# Spectre-Analyzer-SCH_SH2__C.net
KiCad netlist of a schematic drawn in Altium Designer
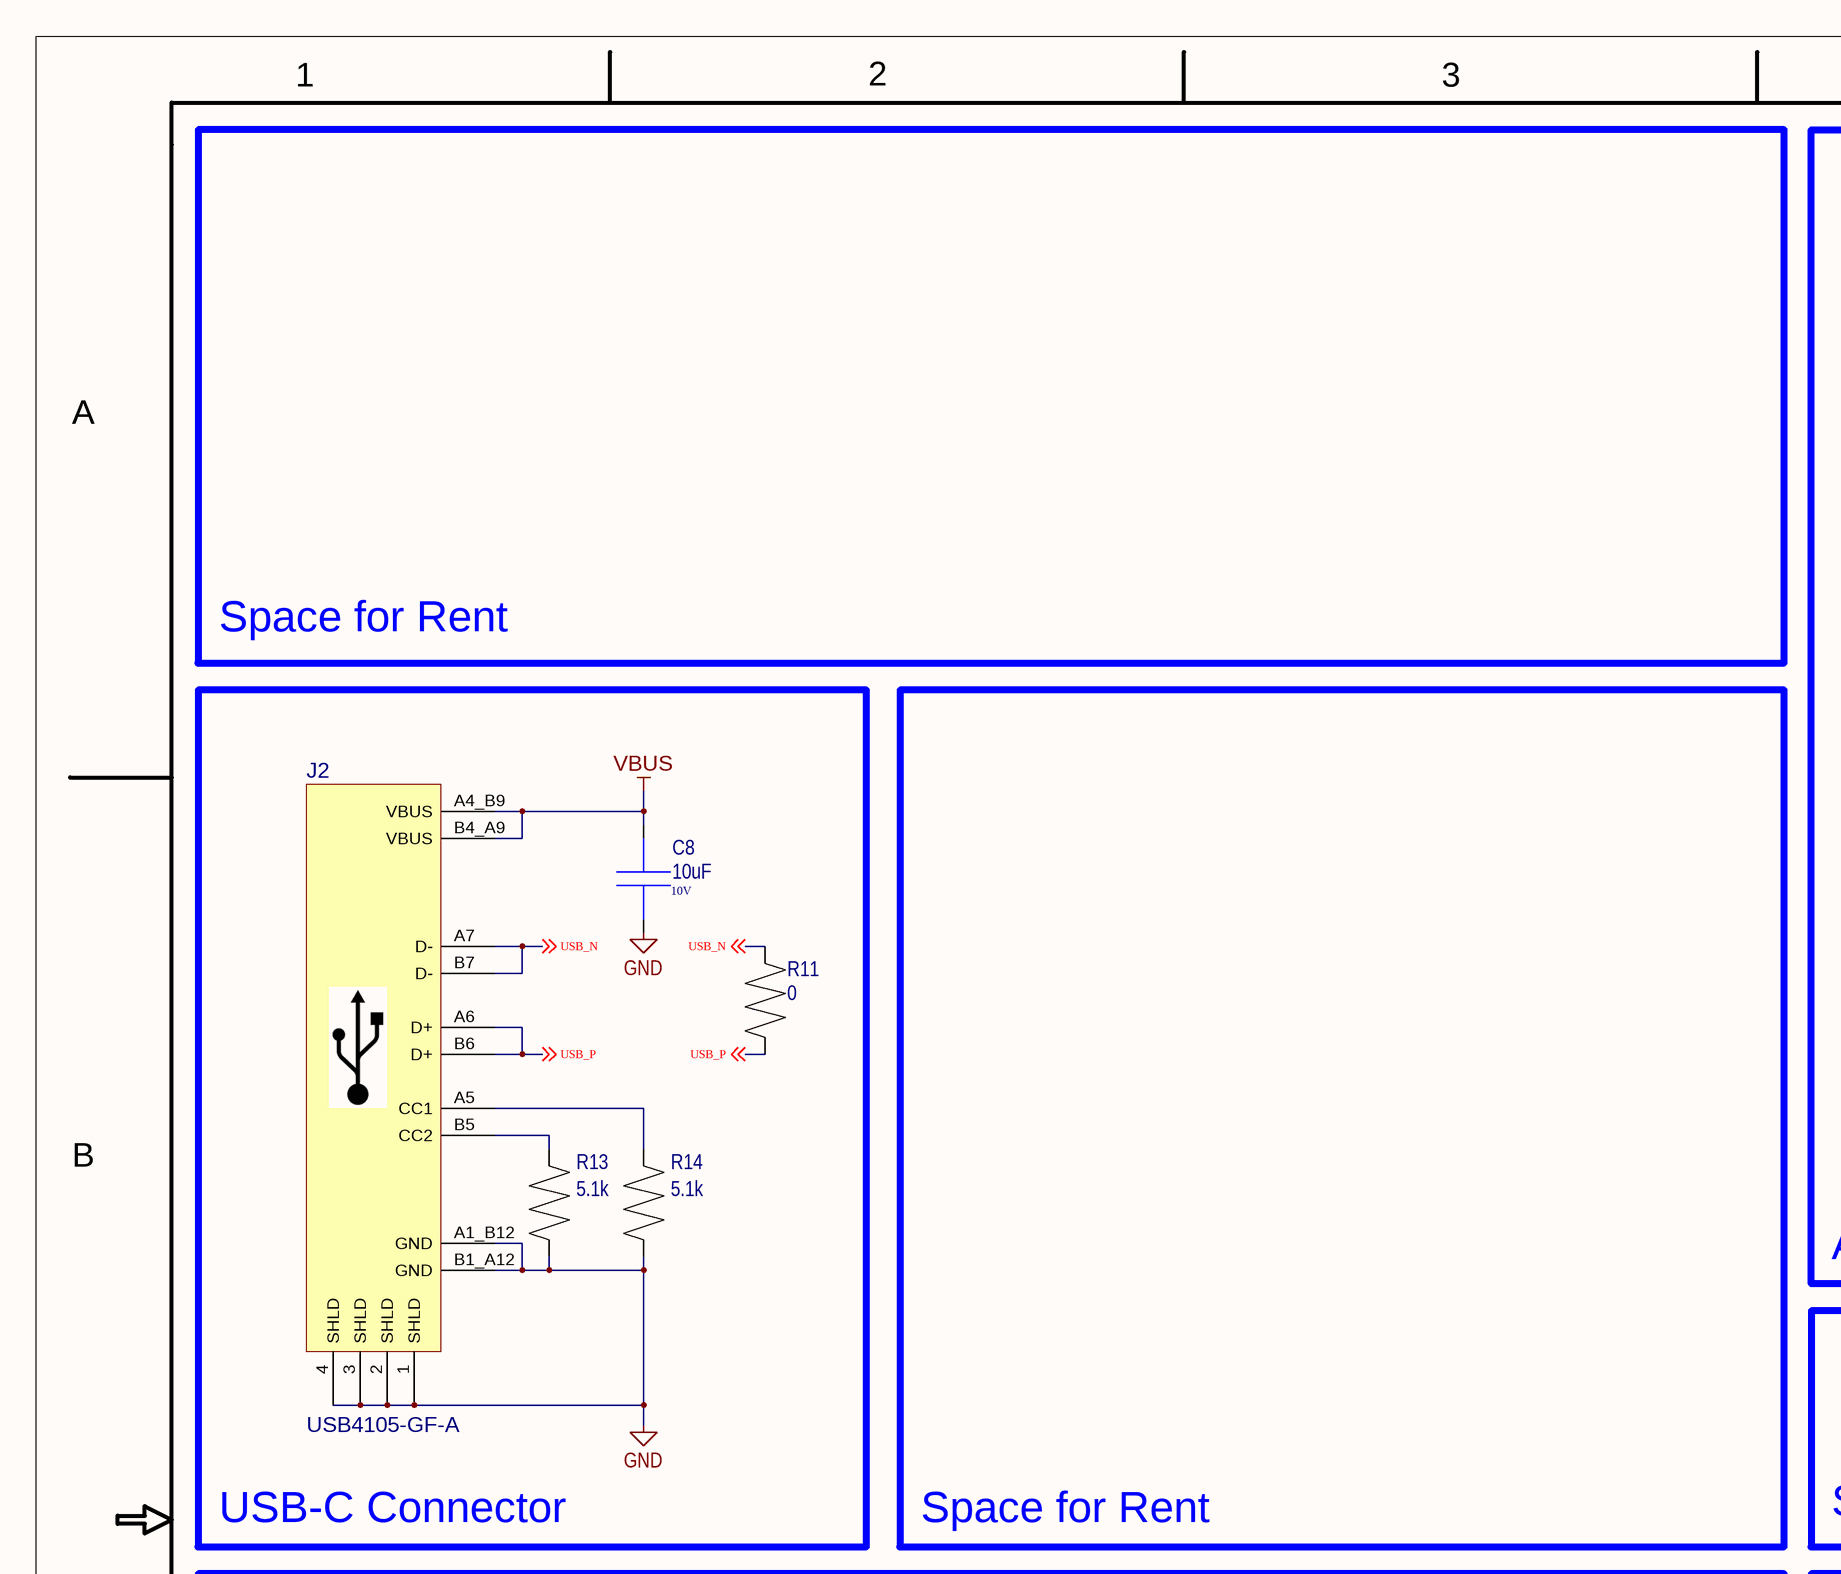
[diagram p0: Spectre-Analyzer-SCH_SH2_(C).SchDoc, top left]
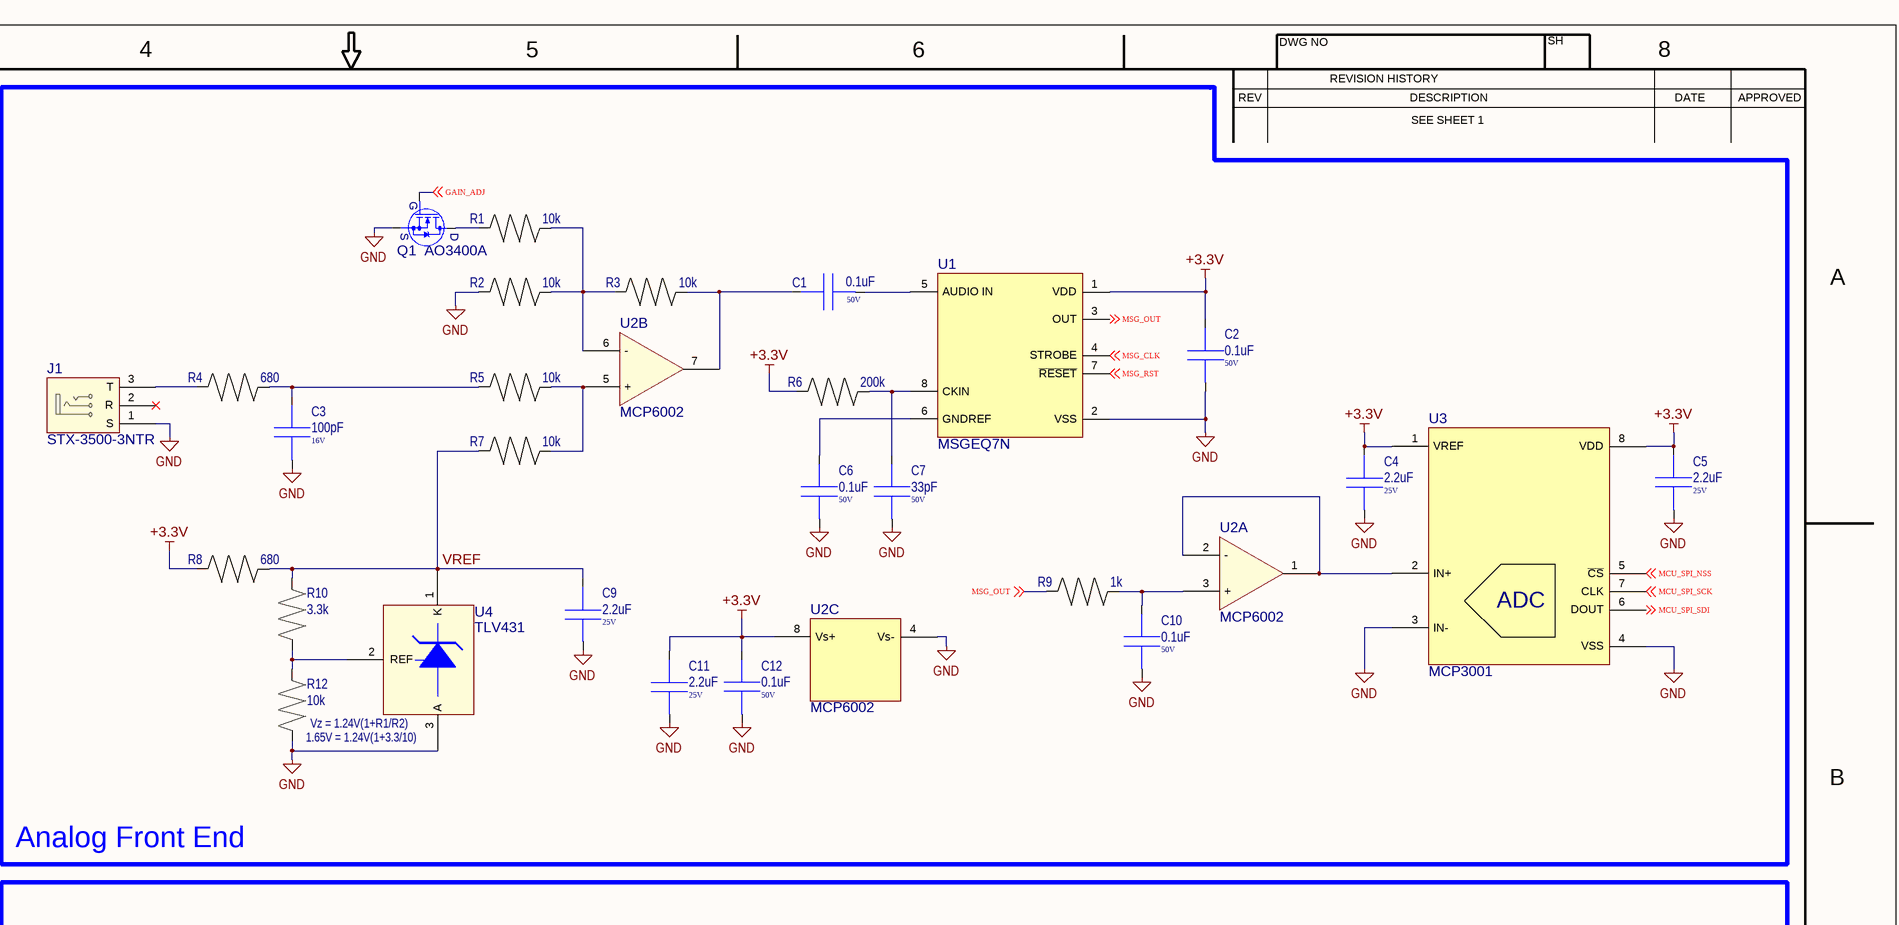
[diagram p1: Spectre-Analyzer-SCH_SH2_(C).SchDoc, top right]
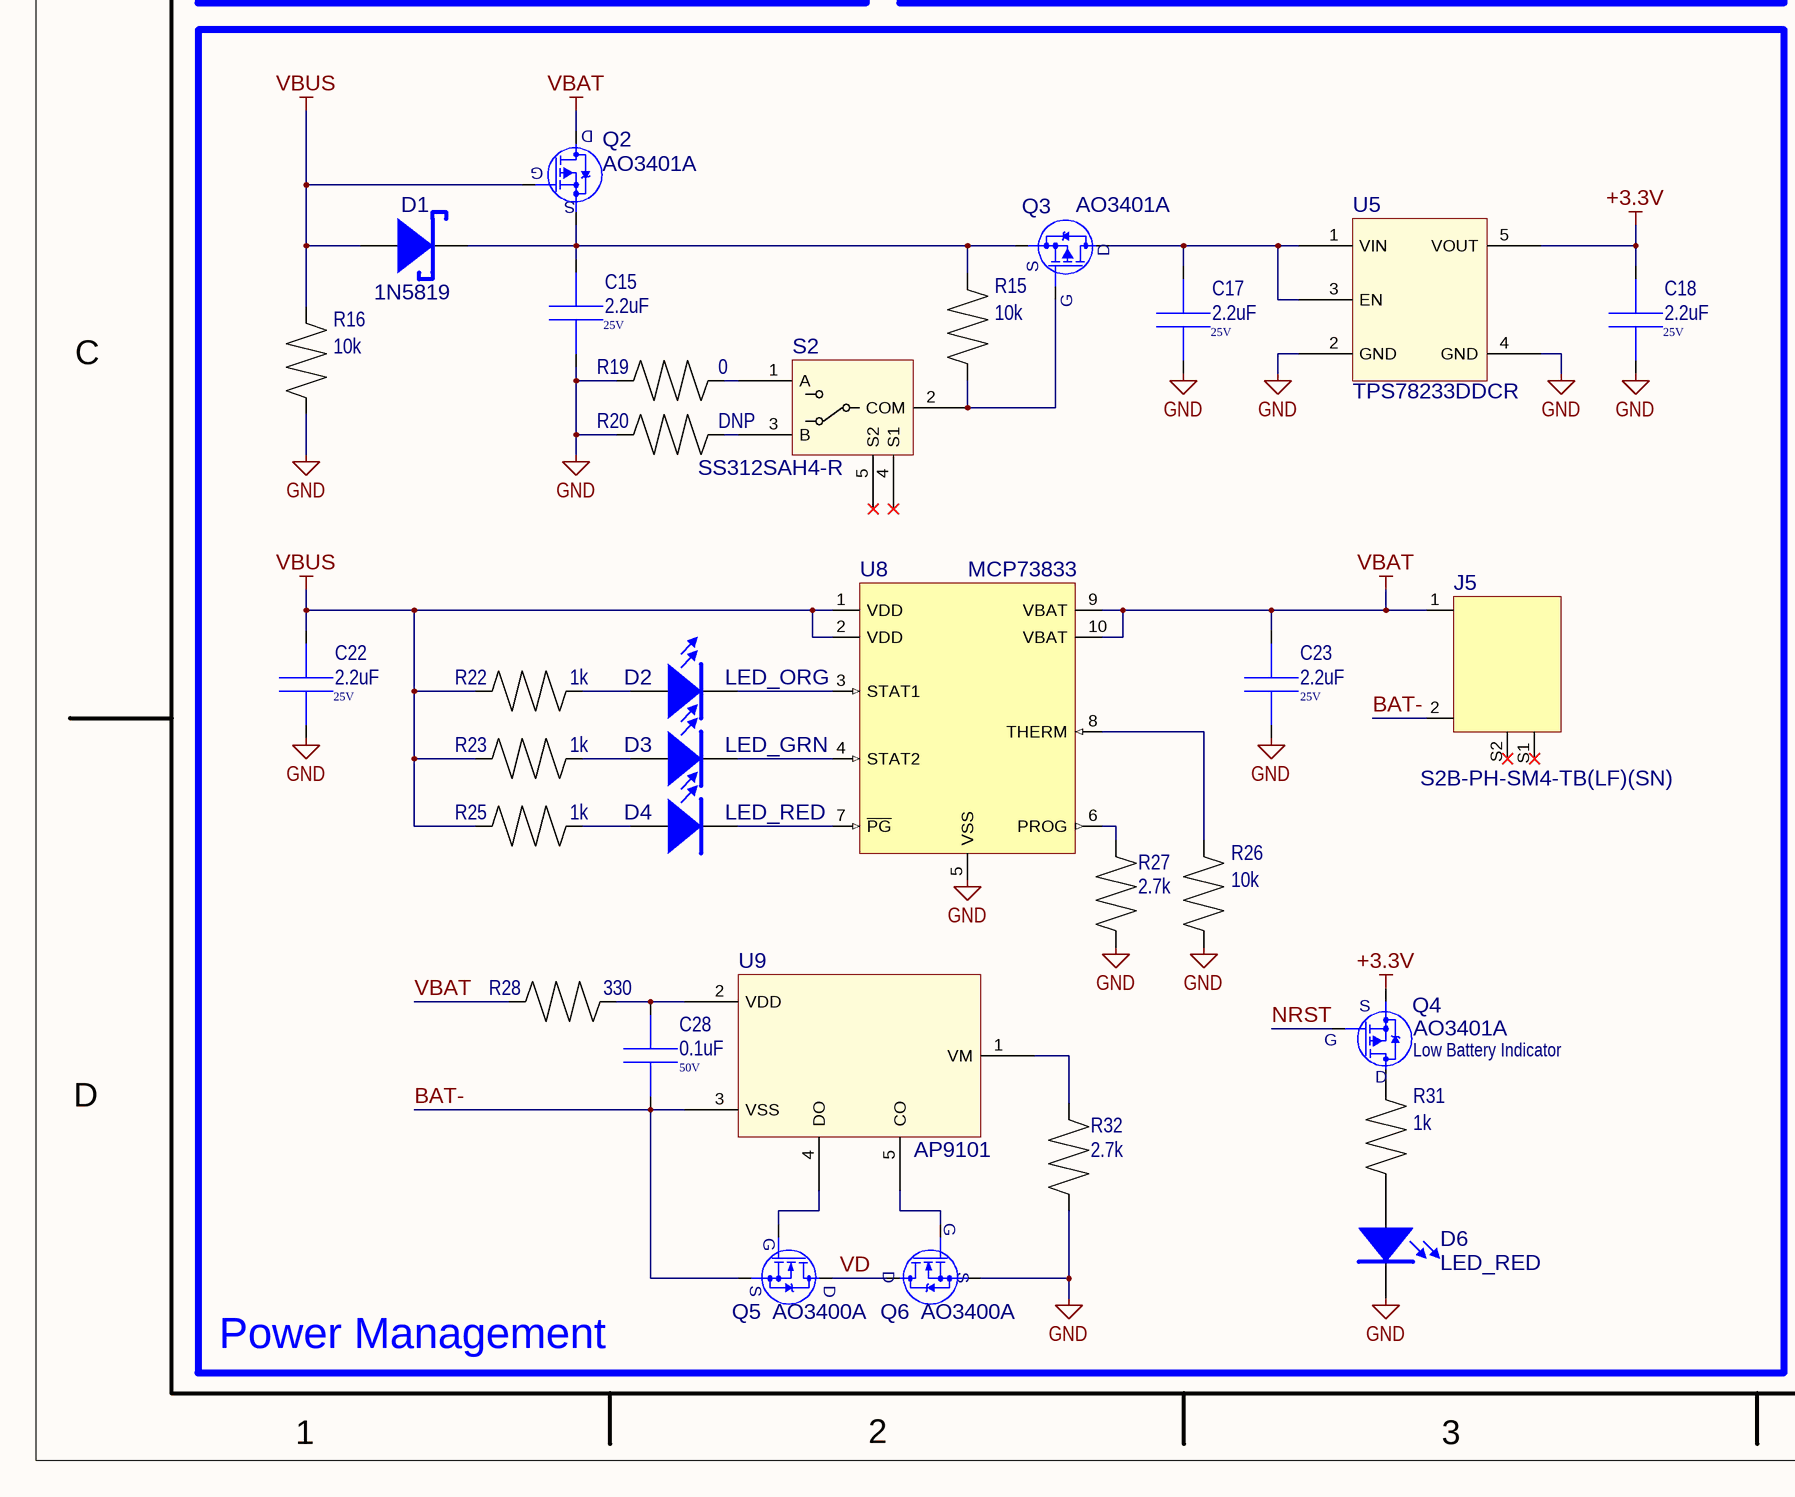
[diagram p2: Spectre-Analyzer-SCH_SH2_(C).SchDoc, bottom left]
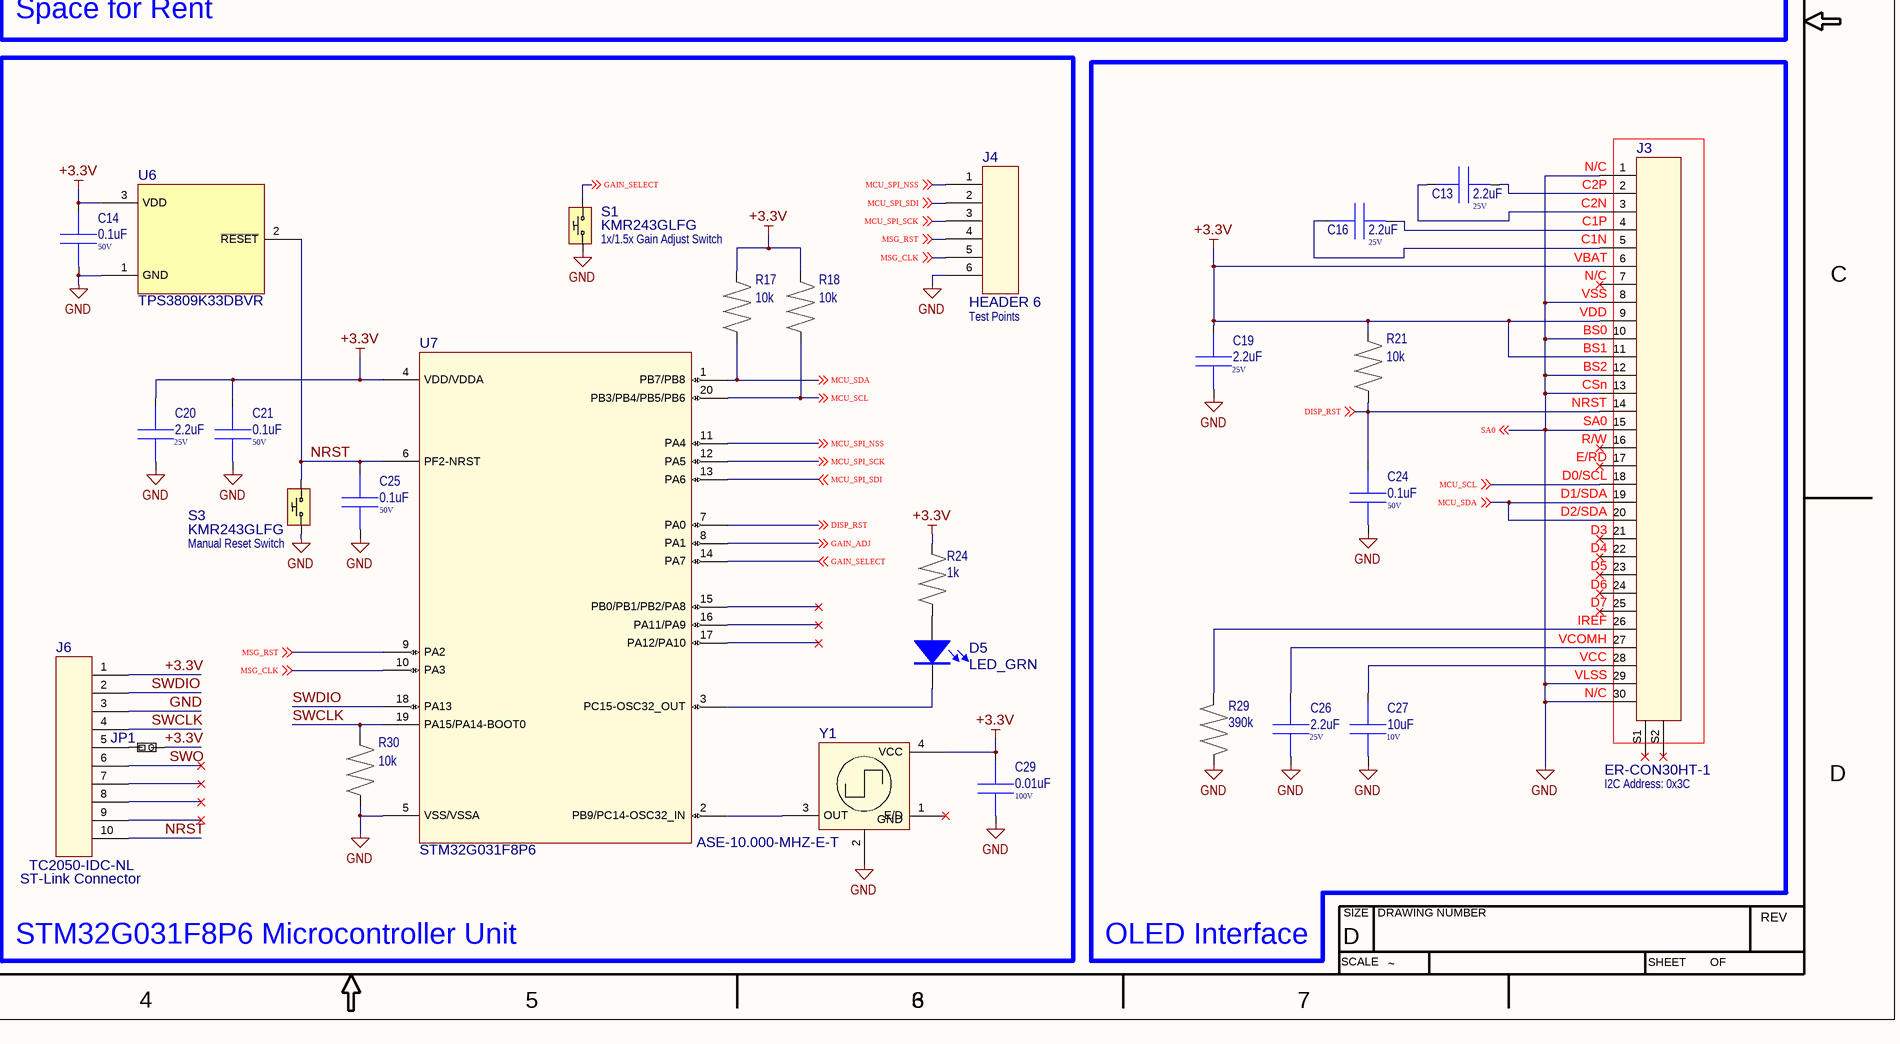
[diagram p3: Spectre-Analyzer-SCH_SH2_(C).SchDoc, bottom right]

(export (version "E")
  (design (tool "Eeschema 10.0.6"))
  (components
    (comp (ref "C1")
      (value "0.1uF")
      (footprint "0402")
      (description "CAP CER 0.1UF 50V X7R 0402")
      (fields
        (field (name "PART NUMBER") "UMK105B7104KVHF")
        (field (name "MANUFACTURER") "Taiyo Yuden")
        (field (name "VOLTAGE") "50V")
      )
      (libsource (lib "CAPACITORS") (part "CAP"))
    )
    (comp (ref "C2")
      (value "0.1uF")
      (footprint "0402")
      (description "CAP CER 0.1UF 50V X7R 0402")
      (fields
        (field (name "PART NUMBER") "UMK105B7104KVHF")
        (field (name "MANUFACTURER") "Taiyo Yuden")
        (field (name "VOLTAGE") "50V")
      )
      (libsource (lib "CAPACITORS") (part "CAP"))
    )
    (comp (ref "C3")
      (value "100pF")
      (footprint "0402")
      (description "CAP CER 100PF 16V X7R 0402")
      (fields
        (field (name "PART NUMBER") "VJ0402Y101KXJCW1BC")
        (field (name "MANUFACTURER") "Vishay Vitramon")
        (field (name "VOLTAGE") "16V")
      )
      (libsource (lib "CAPACITORS") (part "CAP"))
    )
    (comp (ref "C4")
      (value "2.2uF")
      (footprint "0402")
      (description "CAP CER 2.2UF 25V X5R 0402")
      (fields
        (field (name "PART NUMBER") "GRM155R61E225KE11D")
        (field (name "MANUFACTURER") "Murata Electronics")
        (field (name "VOLTAGE") "25V")
      )
      (libsource (lib "CAPACITORS") (part "CAP"))
    )
    (comp (ref "C5")
      (value "2.2uF")
      (footprint "0402")
      (description "CAP CER 2.2UF 25V X5R 0402")
      (fields
        (field (name "PART NUMBER") "GRM155R61E225KE11D")
        (field (name "MANUFACTURER") "Murata Electronics")
        (field (name "VOLTAGE") "25V")
      )
      (libsource (lib "CAPACITORS") (part "CAP"))
    )
    (comp (ref "C6")
      (value "0.1uF")
      (footprint "0402")
      (description "CAP CER 0.1UF 50V X7R 0402")
      (fields
        (field (name "PART NUMBER") "UMK105B7104KVHF")
        (field (name "MANUFACTURER") "Taiyo Yuden")
        (field (name "VOLTAGE") "50V")
      )
      (libsource (lib "CAPACITORS") (part "CAP"))
    )
    (comp (ref "C7")
      (value "33pF")
      (footprint "0402")
      (description "CAP CER 33PF 50V X7R 0402")
      (fields
        (field (name "PART NUMBER") "04025C330JAT2A")
        (field (name "MANUFACTURER") "KYOCERA AVX")
        (field (name "VOLTAGE") "50V")
      )
      (libsource (lib "CAPACITORS") (part "CAP"))
    )
    (comp (ref "C8")
      (value "10uF")
      (footprint "0402")
      (description "CAP CER 10UF 10V X5R 0402")
      (fields
        (field (name "PART NUMBER") "CL05A106MP5NUNC")
        (field (name "MANUFACTURER") "Samsung Electro-Mechanics")
        (field (name "VOLTAGE") "10V")
      )
      (libsource (lib "CAPACITORS") (part "CAP"))
    )
    (comp (ref "C9")
      (value "2.2uF")
      (footprint "0402")
      (description "CAP CER 2.2UF 25V X5R 0402")
      (fields
        (field (name "PART NUMBER") "GRM155R61E225KE11D")
        (field (name "MANUFACTURER") "Murata Electronics")
        (field (name "VOLTAGE") "25V")
      )
      (libsource (lib "CAPACITORS") (part "CAP"))
    )
    (comp (ref "C10")
      (value "0.1uF")
      (footprint "0402")
      (description "CAP CER 0.1UF 50V X7R 0402")
      (fields
        (field (name "PART NUMBER") "UMK105B7104KVHF")
        (field (name "MANUFACTURER") "Taiyo Yuden")
        (field (name "VOLTAGE") "50V")
      )
      (libsource (lib "CAPACITORS") (part "CAP"))
    )
    (comp (ref "C11")
      (value "2.2uF")
      (footprint "0402")
      (description "CAP CER 2.2UF 25V X5R 0402")
      (fields
        (field (name "PART NUMBER") "GRM155R61E225KE11D")
        (field (name "MANUFACTURER") "Murata Electronics")
        (field (name "VOLTAGE") "25V")
      )
      (libsource (lib "CAPACITORS") (part "CAP"))
    )
    (comp (ref "C12")
      (value "0.1uF")
      (footprint "0402")
      (description "CAP CER 0.1UF 50V X7R 0402")
      (fields
        (field (name "PART NUMBER") "UMK105B7104KVHF")
        (field (name "MANUFACTURER") "Taiyo Yuden")
        (field (name "VOLTAGE") "50V")
      )
      (libsource (lib "CAPACITORS") (part "CAP"))
    )
    (comp (ref "C13")
      (value "2.2uF")
      (footprint "0402")
      (description "CAP CER 2.2UF 25V X5R 0402")
      (fields
        (field (name "PART NUMBER") "GRM188C81A106MA73D")
        (field (name "MANUFACTURER") "Murata Electronics")
        (field (name "VOLTAGE") "25V")
      )
      (libsource (lib "CAPACITORS") (part "CAP"))
    )
    (comp (ref "C14")
      (value "0.1uF")
      (footprint "0402")
      (description "CAP CER 0.1UF 50V X7R 0402")
      (fields
        (field (name "PART NUMBER") "UMK105B7104KVHF")
        (field (name "MANUFACTURER") "Taiyo Yuden")
        (field (name "VOLTAGE") "50V")
      )
      (libsource (lib "CAPACITORS") (part "CAP"))
    )
    (comp (ref "C15")
      (value "2.2uF")
      (footprint "0402")
      (description "CAP CER 2.2UF 25V X5R 0402")
      (fields
        (field (name "PART NUMBER") "GRM155R61E225KE11D")
        (field (name "MANUFACTURER") "Murata Electronics")
        (field (name "VOLTAGE") "25V")
      )
      (libsource (lib "CAPACITORS") (part "CAP"))
    )
    (comp (ref "C16")
      (value "2.2uF")
      (footprint "0402")
      (description "CAP CER 2.2UF 25V X5R 0402")
      (fields
        (field (name "PART NUMBER") "GRM188C81A106MA73D")
        (field (name "MANUFACTURER") "Murata Electronics")
        (field (name "VOLTAGE") "25V")
      )
      (libsource (lib "CAPACITORS") (part "CAP"))
    )
    (comp (ref "C17")
      (value "2.2uF")
      (footprint "0402")
      (description "CAP CER 2.2UF 25V X5R 0402")
      (fields
        (field (name "PART NUMBER") "GRM155R61E225KE11D")
        (field (name "MANUFACTURER") "Murata Electronics")
        (field (name "VOLTAGE") "25V")
      )
      (libsource (lib "CAPACITORS") (part "CAP"))
    )
    (comp (ref "C18")
      (value "2.2uF")
      (footprint "0402")
      (description "CAP CER 2.2UF 25V X5R 0402")
      (fields
        (field (name "PART NUMBER") "GRM155R61E225KE11D")
        (field (name "MANUFACTURER") "Murata Electronics")
        (field (name "VOLTAGE") "25V")
      )
      (libsource (lib "CAPACITORS") (part "CAP"))
    )
    (comp (ref "C19")
      (value "2.2uF")
      (footprint "0402")
      (description "CAP CER 2.2UF 25V X5R 0402")
      (fields
        (field (name "PART NUMBER") "GRM188C81A106MA73D")
        (field (name "MANUFACTURER") "Murata Electronics")
        (field (name "VOLTAGE") "25V")
      )
      (libsource (lib "CAPACITORS") (part "CAP"))
    )
    (comp (ref "C20")
      (value "2.2uF")
      (footprint "0402")
      (description "CAP CER 2.2UF 25V X5R 0402")
      (fields
        (field (name "PART NUMBER") "GRM155R61E225KE11D")
        (field (name "MANUFACTURER") "Murata Electronics")
        (field (name "VOLTAGE") "25V")
      )
      (libsource (lib "CAPACITORS") (part "CAP"))
    )
    (comp (ref "C21")
      (value "0.1uF")
      (footprint "0402")
      (description "CAP CER 0.1UF 50V X7R 0402")
      (fields
        (field (name "PART NUMBER") "UMK105B7104KVHF")
        (field (name "MANUFACTURER") "Taiyo Yuden")
        (field (name "VOLTAGE") "50V")
      )
      (libsource (lib "CAPACITORS") (part "CAP"))
    )
    (comp (ref "C22")
      (value "2.2uF")
      (footprint "0402")
      (description "CAP CER 2.2UF 25V X5R 0402")
      (fields
        (field (name "PART NUMBER") "GRM155R61E225KE11D")
        (field (name "MANUFACTURER") "Murata Electronics")
        (field (name "VOLTAGE") "25V")
      )
      (libsource (lib "CAPACITORS") (part "CAP"))
    )
    (comp (ref "C23")
      (value "2.2uF")
      (footprint "0402")
      (description "CAP CER 2.2UF 25V X5R 0402")
      (fields
        (field (name "PART NUMBER") "GRM155R61E225KE11D")
        (field (name "MANUFACTURER") "Murata Electronics")
        (field (name "VOLTAGE") "25V")
      )
      (libsource (lib "CAPACITORS") (part "CAP"))
    )
    (comp (ref "C24")
      (value "0.1uF")
      (footprint "0402")
      (description "CAP CER 0.1UF 50V X7R 0402")
      (fields
        (field (name "PART NUMBER") "UMK105B7104KVHF")
        (field (name "MANUFACTURER") "Taiyo Yuden")
        (field (name "VOLTAGE") "50V")
      )
      (libsource (lib "CAPACITORS") (part "CAP"))
    )
    (comp (ref "C25")
      (value "0.1uF")
      (footprint "0402")
      (description "CAP CER 0.1UF 50V X7R 0402")
      (fields
        (field (name "PART NUMBER") "UMK105B7104KVHF")
        (field (name "MANUFACTURER") "Taiyo Yuden")
        (field (name "VOLTAGE") "50V")
      )
      (libsource (lib "CAPACITORS") (part "CAP"))
    )
    (comp (ref "C26")
      (value "2.2uF")
      (footprint "0402")
      (description "CAP CER 2.2UF 25V X5R 0402")
      (fields
        (field (name "PART NUMBER") "GRM188C81A106MA73D")
        (field (name "MANUFACTURER") "Murata Electronics")
        (field (name "VOLTAGE") "25V")
      )
      (libsource (lib "CAPACITORS") (part "CAP"))
    )
    (comp (ref "C27")
      (value "10uF")
      (footprint "0402")
      (description "CAP CER 10UF 10V X5R 0402")
      (fields
        (field (name "PART NUMBER") "CL05A106MP5NUNC")
        (field (name "MANUFACTURER") "Samsung Electro-Mechanics")
        (field (name "VOLTAGE") "10V")
      )
      (libsource (lib "CAPACITORS") (part "CAP"))
    )
    (comp (ref "C28")
      (value "0.1uF")
      (footprint "0402")
      (description "CAP CER 0.1UF 50V X7R 0402")
      (fields
        (field (name "PART NUMBER") "UMK105B7104KVHF")
        (field (name "MANUFACTURER") "Taiyo Yuden")
        (field (name "VOLTAGE") "50V")
      )
      (libsource (lib "CAPACITORS") (part "CAP"))
    )
    (comp (ref "C29")
      (value "0.01uF")
      (footprint "0402")
      (description "CAP CER 0.01UF 100V X7R 0402")
      (fields
        (field (name "PART NUMBER") "HMR105B7103MV-F")
        (field (name "MANUFACTURER") "Taiyo Yuden")
        (field (name "VOLTAGE") "100V")
      )
      (libsource (lib "CAPACITORS") (part "CAP"))
    )
    (comp (ref "D1")
      (value "1N5819")
      (footprint "SOD-123")
      (description "DIODE SCHOTTKY 40V 1A SOD123")
      (fields (field (name "MANUFACTURER") "Diodes Incorporated") (field (name "PART NUMBER") "1N5819HW-7-F"))
      (libsource (lib "SEMICONDUCTORS") (part "DIODE_SCHOTTKY"))
    )
    (comp (ref "D2")
      (value "LED_ORG")
      (footprint "0603_LED_Red")
      (description "Standard LEDs - SMD HE Red 645 nm Water Clear")
      (fields (field (name "PART NUMBER") "SM0603HCL") (field (name "MANUFACTURER") "Bivar"))
      (libsource (lib "SEMICONDUCTORS") (part "LED_Red"))
    )
    (comp (ref "D3")
      (value "LED_GRN")
      (footprint "0603_LED_Red")
      (description "Standard LEDs - SMD HE Red 645 nm Water Clear")
      (fields (field (name "PART NUMBER") "SM0603HCL") (field (name "MANUFACTURER") "Bivar"))
      (libsource (lib "SEMICONDUCTORS") (part "LED_Red"))
    )
    (comp (ref "D4")
      (value "LED_RED")
      (footprint "0603_LED_Red")
      (description "Standard LEDs - SMD HE Red 645 nm Water Clear")
      (fields (field (name "PART NUMBER") "SM0603HCL") (field (name "MANUFACTURER") "Bivar"))
      (libsource (lib "SEMICONDUCTORS") (part "LED_Red"))
    )
    (comp (ref "D5")
      (value "LED_GRN")
      (footprint "0603_LED_Red")
      (description "Standard LEDs - SMD HE Red 645 nm Water Clear")
      (fields (field (name "PART NUMBER") "SM0603HCL") (field (name "MANUFACTURER") "Bivar"))
      (libsource (lib "SEMICONDUCTORS") (part "LED_Red"))
    )
    (comp (ref "D6")
      (value "LED_RED")
      (footprint "0603_LED_Red")
      (description "Standard LEDs - SMD HE Red 645 nm Water Clear")
      (fields (field (name "PART NUMBER") "SM0603HCL") (field (name "MANUFACTURER") "Bivar"))
      (libsource (lib "SEMICONDUCTORS") (part "LED_Red"))
    )
    (comp (ref "J1")
      (value "STX-3500-3NTR")
      (footprint "STX-3500-3NTR")
      (description "CONN JACK STEREO 3.5MM SMD R/A")
      (fields (field (name "MANUFACTURER") "Kycon, Inc."))
      (libsource (lib "ConnectorLib") (part "STX-3500-3NTR"))
    )
    (comp (ref "J2")
      (value "USB4105-GF-A")
      (footprint "USB4105-GF-A")
      (description "CONN RCP USB2.0 TYP C 24P SMD RA")
      (fields (field (name "MANUFACTURER") "GCT"))
      (libsource (lib "Connectors") (part "USB4105-GF-A"))
    )
    (comp (ref "J3")
      (value "ER-CON30HT-1")
      (footprint "ER-CON30HT-1")
      (description "30 PINS 0.5 PITCH SMD TOP CONTACT CONN")
      (fields (field (name "MANUFACTURER") "EastRising Technology"))
      (libsource (lib "ConnectorLib") (part "ER-CON30HT-1"))
    )
    (comp (ref "J4")
      (value "HEADER 6")
      (footprint "801-43-006-10-012000")
      (description "CONN SOCKET STRIP 6 POS 0.1\"")
      (fields (field (name "MANUFACTURER") "Mill-Max") (field (name "PART NUMBER") "801-43-006-10-012000"))
      (libsource (lib "ConnectorLib") (part "801-43-006-10-012000"))
    )
    (comp (ref "J5")
      (value "S2B-PH-SM4-TB(LF)(SN)")
      (footprint "S2B-PH-SM4-TB(LF)(SN)")
      (description "CONN HEADER SMD R/A 2POS 2MM")
      (fields (field (name "MANUFACTURER") "JST Sales America Inc."))
      (libsource (lib "ConnectorLib") (part "S2B-PH-SM4-TB(LF)(SN)"))
    )
    (comp (ref "J6")
      (value "TC2050-IDC-NL")
      (footprint "TC2050-IDC-NL-FP")
      (description "CBL PLUG-OF-NAILS 10-PIN")
      (fields (field (name "MANUFACTURER") "Tag-Connect LLC"))
      (libsource (lib "Connectors") (part "TC2050-IDC-NL"))
    )
    (comp (ref "JP1")
      (value "Solder Jumper")
      (footprint "SOLDER JUMPER")
      (description "Solder Jumper Single 0.5mm Pitch")
      (libsource (lib "ConnectorLib") (part "SolderJumper_Single"))
    )
    (comp (ref "Q1")
      (value "AO3400A")
      (footprint "SOT-23-3")
      (description "MOSFET N-CH 30V 5.7A SOT23-3L")
      (fields (field (name "MANUFACTURER") "Alpha & Omega Semiconductor Inc."))
      (libsource (lib "SEMICONDUCTORS") (part "MOSFET_N"))
    )
    (comp (ref "Q2")
      (value "AO3401A")
      (footprint "SOT-23")
      (description "MOSFET P-CH 30V 4A SOT23-3L")
      (fields (field (name "MANUFACTURER") "Alpha & Omega Semiconductor Inc."))
      (libsource (lib "SEMICONDUCTORS") (part "MOSFET_P"))
    )
    (comp (ref "Q3")
      (value "AO3401A")
      (footprint "SOT-23")
      (description "MOSFET P-CH 30V 4A SOT23-3L")
      (fields (field (name "MANUFACTURER") "Alpha & Omega Semiconductor Inc."))
      (libsource (lib "") (part "MOSFET_P_2"))
    )
    (comp (ref "Q4")
      (value "AO3401A")
      (footprint "SOT-23")
      (description "MOSFET P-CH 30V 4A SOT23-3L")
      (fields (field (name "MANUFACTURER") "Alpha & Omega Semiconductor Inc."))
      (libsource (lib "") (part "MOSFET_P_1"))
    )
    (comp (ref "Q5")
      (value "AO3400A")
      (footprint "SOT-23-3")
      (description "MOSFET N-CH 30V 5.7A SOT23-3L")
      (fields (field (name "MANUFACTURER") "Alpha & Omega Semiconductor Inc."))
      (libsource (lib "SEMICONDUCTORS") (part "MOSFET_N"))
    )
    (comp (ref "Q6")
      (value "AO3400A")
      (footprint "SOT-23-3")
      (description "MOSFET N-CH 30V 5.7A SOT23-3L")
      (fields (field (name "MANUFACTURER") "Alpha & Omega Semiconductor Inc."))
      (libsource (lib "") (part "MOSFET_N_1"))
    )
    (comp (ref "R1")
      (value "10k")
      (footprint "0402")
      (description "RES SMD 10K OHM 1% 1/16W 0402")
      (fields (field (name "PART NUMBER") "CR0402-FX-1002GLF") (field (name "MANUFACTURER") "Bourns"))
      (libsource (lib "RESISTORS") (part "RES"))
    )
    (comp (ref "R2")
      (value "10k")
      (footprint "0402")
      (description "RES SMD 10K OHM 1% 1/16W 0402")
      (fields (field (name "PART NUMBER") "CR0402-FX-1002GLF") (field (name "MANUFACTURER") "Bourns"))
      (libsource (lib "RESISTORS") (part "RES"))
    )
    (comp (ref "R3")
      (value "10k")
      (footprint "0402")
      (description "RES SMD 10K OHM 1% 1/16W 0402")
      (fields (field (name "PART NUMBER") "CR0402-FX-1002GLF") (field (name "MANUFACTURER") "Bourns"))
      (libsource (lib "RESISTORS") (part "RES"))
    )
    (comp (ref "R4")
      (value "680")
      (footprint "0402")
      (description "RES SMD 680 OHM 1% 1/16W 0402")
      (fields (field (name "PART NUMBER") "CR0402-FX-6800GLF") (field (name "MANUFACTURER") "Bourns"))
      (libsource (lib "RESISTORS") (part "RES"))
    )
    (comp (ref "R5")
      (value "10k")
      (footprint "0402")
      (description "RES SMD 10K OHM 1% 1/16W 0402")
      (fields (field (name "PART NUMBER") "CR0402-FX-1002GLF") (field (name "MANUFACTURER") "Bourns"))
      (libsource (lib "RESISTORS") (part "RES"))
    )
    (comp (ref "R6")
      (value "200k")
      (footprint "0402")
      (description "RES SMD 200K OHM 1% 1/16W 0402")
      (fields (field (name "PART NUMBER") "CR0402-FX-2003GLF") (field (name "MANUFACTURER") "Bourns"))
      (libsource (lib "RESISTORS") (part "RES"))
    )
    (comp (ref "R7")
      (value "10k")
      (footprint "0402")
      (description "RES SMD 10K OHM 1% 1/16W 0402")
      (fields (field (name "PART NUMBER") "CR0402-FX-1002GLF") (field (name "MANUFACTURER") "Bourns"))
      (libsource (lib "RESISTORS") (part "RES"))
    )
    (comp (ref "R8")
      (value "680")
      (footprint "0402")
      (description "RES SMD 680 OHM 1% 1/16W 0402")
      (fields (field (name "PART NUMBER") "CR0402-FX-6800GLF") (field (name "MANUFACTURER") "Bourns"))
      (libsource (lib "RESISTORS") (part "RES"))
    )
    (comp (ref "R9")
      (value "1k")
      (footprint "0402")
      (description "RES 1K OHM 1% 1/16W 0402")
      (fields (field (name "PART NUMBER") "CR0402AFX-1001GLF") (field (name "MANUFACTURER") "Bourns"))
      (libsource (lib "RESISTORS") (part "RES"))
    )
    (comp (ref "R10")
      (value "3.3k")
      (footprint "0402")
      (description "RES SMD 3.3K OHM 1% 1/16W 0402")
      (fields (field (name "PART NUMBER") "CR0402-FX-3301GLF") (field (name "MANUFACTURER") "Bourns"))
      (libsource (lib "RESISTORS") (part "RES"))
    )
    (comp (ref "R11")
      (value "0")
      (footprint "0402")
      (description "Thick Film Resistors - SMD 1/16watt 0ohm Commercial Use")
      (fields (field (name "PART NUMBER") "CRCW04020000Z0EDC") (field (name "MANUFACTURER") "Vishay / Dale"))
      (libsource (lib "RESISTORS") (part "RES"))
    )
    (comp (ref "R12")
      (value "10k")
      (footprint "0402")
      (description "RES SMD 10K OHM 1% 1/16W 0402")
      (fields (field (name "PART NUMBER") "CR0402-FX-1002GLF") (field (name "MANUFACTURER") "Bourns"))
      (libsource (lib "RESISTORS") (part "RES"))
    )
    (comp (ref "R13")
      (value "5.1k")
      (footprint "0402")
      (description "RES SMD 5.1K OHM 1% 1/16W 0402")
      (fields (field (name "PART NUMBER") "CRCW04025K10FKED") (field (name "MANUFACTURER") "Vishay / Dale"))
      (libsource (lib "RESISTORS") (part "RES"))
    )
    (comp (ref "R14")
      (value "5.1k")
      (footprint "0402")
      (description "RES SMD 5.1K OHM 1% 1/16W 0402")
      (fields (field (name "PART NUMBER") "CRCW04025K10FKED") (field (name "MANUFACTURER") "Vishay / Dale"))
      (libsource (lib "RESISTORS") (part "RES"))
    )
    (comp (ref "R15")
      (value "10k")
      (footprint "0402")
      (description "RES SMD 10K OHM 1% 1/16W 0402")
      (fields (field (name "PART NUMBER") "CR0402-FX-1002GLF") (field (name "MANUFACTURER") "Bourns"))
      (libsource (lib "RESISTORS") (part "RES"))
    )
    (comp (ref "R16")
      (value "10k")
      (footprint "0402")
      (description "RES SMD 10K OHM 1% 1/16W 0402")
      (fields (field (name "PART NUMBER") "CR0402-FX-1002GLF") (field (name "MANUFACTURER") "Bourns"))
      (libsource (lib "RESISTORS") (part "RES"))
    )
    (comp (ref "R17")
      (value "10k")
      (footprint "0402")
      (description "RES SMD 10K OHM 1% 1/16W 0402")
      (fields (field (name "PART NUMBER") "CR0402-FX-1002GLF") (field (name "MANUFACTURER") "Bourns"))
      (libsource (lib "RESISTORS") (part "RES"))
    )
    (comp (ref "R18")
      (value "10k")
      (footprint "0402")
      (description "RES SMD 10K OHM 1% 1/16W 0402")
      (fields (field (name "PART NUMBER") "CR0402-FX-1002GLF") (field (name "MANUFACTURER") "Bourns"))
      (libsource (lib "RESISTORS") (part "RES"))
    )
    (comp (ref "R19")
      (value "0")
      (footprint "0402")
      (description "Thick Film Resistors - SMD 1/16watt 0ohm Commercial Use")
      (fields (field (name "PART NUMBER") "CRCW04020000Z0EDC") (field (name "MANUFACTURER") "Vishay / Dale"))
      (libsource (lib "RESISTORS") (part "RES"))
    )
    (comp (ref "R20")
      (value "DNP")
      (footprint "0402")
      (description "Thick Film Resistors - SMD 1/16watt 0ohm Commercial Use")
      (fields (field (name "PART NUMBER") "CRCW04020000Z0EDC") (field (name "MANUFACTURER") "Vishay / Dale"))
      (libsource (lib "RESISTORS") (part "RES"))
    )
    (comp (ref "R21")
      (value "10k")
      (footprint "0402")
      (description "RES SMD 10K OHM 1% 1/16W 0402")
      (fields (field (name "PART NUMBER") "CR0402-FX-1002GLF") (field (name "MANUFACTURER") "Bourns"))
      (libsource (lib "RESISTORS") (part "RES"))
    )
    (comp (ref "R22")
      (value "1k")
      (footprint "0402")
      (description "RES 1K OHM 1% 1/16W 0402")
      (fields (field (name "PART NUMBER") "CR0402AFX-1001GLF") (field (name "MANUFACTURER") "Bourns"))
      (libsource (lib "RESISTORS") (part "RES"))
    )
    (comp (ref "R23")
      (value "1k")
      (footprint "0402")
      (description "RES 1K OHM 1% 1/16W 0402")
      (fields (field (name "PART NUMBER") "CR0402AFX-1001GLF") (field (name "MANUFACTURER") "Bourns"))
      (libsource (lib "RESISTORS") (part "RES"))
    )
    (comp (ref "R24")
      (value "1k")
      (footprint "0402")
      (description "RES 1K OHM 1% 1/16W 0402")
      (fields (field (name "PART NUMBER") "CR0402AFX-1001GLF") (field (name "MANUFACTURER") "Bourns"))
      (libsource (lib "RESISTORS") (part "RES"))
    )
    (comp (ref "R25")
      (value "1k")
      (footprint "0402")
      (description "RES 1K OHM 1% 1/16W 0402")
      (fields (field (name "PART NUMBER") "CR0402AFX-1001GLF") (field (name "MANUFACTURER") "Bourns"))
      (libsource (lib "RESISTORS") (part "RES"))
    )
    (comp (ref "R26")
      (value "10k")
      (footprint "0402")
      (description "RES SMD 10K OHM 1% 1/16W 0402")
      (fields (field (name "PART NUMBER") "CR0402-FX-1002GLF") (field (name "MANUFACTURER") "Bourns"))
      (libsource (lib "RESISTORS") (part "RES"))
    )
    (comp (ref "R27")
      (value "2.7k")
      (footprint "0402")
      (description "RES SMD 2.7K OHM 1% 1/16W 0402")
      (fields (field (name "PART NUMBER") "CR0402-FX-2701GLF") (field (name "MANUFACTURER") "Bourns"))
      (libsource (lib "RESISTORS") (part "RES"))
    )
    (comp (ref "R28")
      (value "330")
      (footprint "0402")
      (description "RES 330 OHM 1% 1/16W 0402")
      (fields (field (name "PART NUMBER") "CR0402AFX-3300GLF") (field (name "MANUFACTURER") "Bourns"))
      (libsource (lib "RESISTORS") (part "RES"))
    )
    (comp (ref "R29")
      (value "390k")
      (footprint "0402")
      (description "RES SMD 390K OHM 1% 1/16W 0402")
      (fields (field (name "PART NUMBER") "CR0402-FX-3903GLF") (field (name "MANUFACTURER") "Bourns Inc."))
      (libsource (lib "RESISTORS") (part "RES"))
    )
    (comp (ref "R30")
      (value "10k")
      (footprint "0402")
      (description "RES SMD 10K OHM 1% 1/16W 0402")
      (fields (field (name "PART NUMBER") "CR0402-FX-1002GLF") (field (name "MANUFACTURER") "Bourns"))
      (libsource (lib "RESISTORS") (part "RES"))
    )
    (comp (ref "R31")
      (value "1k")
      (footprint "0402")
      (description "RES SMD 1K OHM 1% 1/16W 0402")
      (fields (field (name "PART NUMBER") "CR0402-FX-1001GLF") (field (name "MANUFACTURER") "Bourns"))
      (libsource (lib "RESISTORS") (part "RES"))
    )
    (comp (ref "R32")
      (value "2.7k")
      (footprint "0402")
      (description "RES SMD 2.7K OHM 1% 1/16W 0402")
      (fields (field (name "PART NUMBER") "CR0402-FX-2701GLF") (field (name "MANUFACTURER") "Bourns"))
      (libsource (lib "RESISTORS") (part "RES"))
    )
    (comp (ref "S1")
      (value "KMR243GLFG")
      (footprint "KMR 2 Series")
      (description "SWITCH TACTILE SPST-NO 0.01A 32V")
      (fields (field (name "MANUFACTURER") "C&K"))
      (libsource (lib "SwitchesLib") (part "KMR 2 Series"))
    )
    (comp (ref "S2")
      (value "SS312SAH4-R")
      (footprint "SW_SS312SAH4-R")
      (description "SWITCH SLIDE SPDT 0.4VA 28V")
      (fields (field (name "MANUFACTURER") "NKK Switches"))
      (libsource (lib "Switches") (part "SS312SAH4-R"))
    )
    (comp (ref "S3")
      (value "KMR243GLFG")
      (footprint "KMR 2 Series")
      (description "SWITCH TACTILE SPST-NO 0.01A 32V")
      (fields (field (name "MANUFACTURER") "C&K"))
      (libsource (lib "SwitchesLib") (part "KMR 2 Series"))
    )
    (comp (ref "U1")
      (value "MSGEQ7N")
      (footprint "SOIC-8")
      (description "SWITCHED CAPA AUDIO ANALYZER SOIC-8")
      (fields (field (name "MANUFACTURER") "Mixed Signal Integrated"))
      (libsource (lib "Sensors") (part "MSGEQ7"))
    )
    (comp (ref "U2")
      (value "MCP6002")
      (footprint "SOIC-8")
      (description "IC OPAMP GP 2 CIRCUIT 8SOIC")
      (fields
        (field (name "PART NUMBER") "MCP6002-E/SN")
        (field (name "MANUFACTURER") "Microchip Technology")
      )
      (libsource (lib "Operational Amplifiers") (part "AD8072"))
    )
    (comp (ref "U3")
      (value "MCP3001")
      (footprint "SOIC-8")
      (description "IC ADC 10BIT SAR 8SOIC")
      (fields
        (field (name "MANUFACTURER") "Microchip Technology")
        (field (name "PART NUMBER") "MCP3001T-I/SN")
      )
      (libsource (lib "Data_Converters") (part "MCP3001"))
    )
    (comp (ref "U4")
      (value "TLV431")
      (footprint "SOT-23-3")
      (description "IC VREF SHUNT ADJ SOT23-3")
      (fields (field (name "MANUFACTURER") "onsemi") (field (name "PART NUMBER") "TLV431ASN1T1G"))
      (libsource (lib "Linear Regulators") (part "TL431xxDBZR"))
    )
    (comp (ref "U5")
      (value "TPS78233DDCR")
      (footprint "TSOT23-5")
      (description "IC REG LINEAR 3.3V 150MA SOT23-5")
      (fields (field (name "MANUFACTURER") "Texas Instruments"))
      (libsource (lib "Linear Regulators") (part "TPS782xxDDCR"))
    )
    (comp (ref "U6")
      (value "TPS3809K33DBVR")
      (footprint "SOT-23-3")
      (description "IC SUPERVISOR 1 CHANNEL SOT23-3")
      (fields (field (name "MANUFACTURER") "Texas Instruments"))
      (libsource (lib "Sensors") (part "TPS3809x"))
    )
    (comp (ref "U7")
      (value "STM32G031F8P6")
      (footprint "TSSOP-20")
      (description "IC MCU 32BIT 64KB FLASH 20TSSOP")
      (fields (field (name "MANUFACTURER") "STMicroelectronics"))
      (libsource (lib "MicrocontrollerUnits") (part "STM32G031FxP6"))
    )
    (comp (ref "U8")
      (value "MCP73833")
      (footprint "MSOP-10")
      (description "IC BATT CNTRL LI-ION 1CEL 10MSOP")
      (fields (field (name "PART NUMBER") "MCP73833-CNI/UN") (field (name "MANUFACTURER") "Microchip"))
      (libsource (lib "Linear Regulators") (part "MCP73833"))
    )
    (comp (ref "U9")
      (value "AP9101")
      (footprint "TSOT23-5")
      (description "IC BATT PROT LI-ION 1CELL SOT25")
      (fields
        (field (name "MANUFACTURER") "Diodes Incorporated")
        (field (name "PART NUMBER") "AP9101CAK-AKTRG1")
      )
      (libsource (lib "Linear Regulators") (part "AP9101CAK-AKTRG1"))
    )
    (comp (ref "Y1")
      (value "ASE-10.000-MHZ-E-T")
      (footprint "ASE-XXXXX-X-X-X")
      (description "OSC XO 10.000MHZ CMOS SMD")
      (fields (field (name "MANUFACTURER") "Abracon"))
      (libsource (lib "Oscillators") (part "ASE-XXXXX-MHZ-X-X"))
    )
  )
  (nets
    (net (code "1") (name "+3.3V") (class "Default")
      (node (ref "C11") (pin "2") (pinfunction "2_2") (pintype "passive"))
      (node (ref "C12") (pin "2") (pinfunction "2_2") (pintype "passive"))
      (node (ref "C14") (pin "2") (pinfunction "2_2") (pintype "passive"))
      (node (ref "C18") (pin "2") (pinfunction "2_2") (pintype "passive"))
      (node (ref "C19") (pin "2") (pinfunction "2_2") (pintype "passive"))
      (node (ref "C2") (pin "2") (pinfunction "2_2") (pintype "passive"))
      (node (ref "C20") (pin "2") (pinfunction "2_2") (pintype "passive"))
      (node (ref "C21") (pin "2") (pinfunction "2_2") (pintype "passive"))
      (node (ref "C29") (pin "2") (pinfunction "2_2") (pintype "passive"))
      (node (ref "C4") (pin "2") (pinfunction "2_2") (pintype "passive"))
      (node (ref "C5") (pin "2") (pinfunction "2_2") (pintype "passive"))
      (node (ref "J3") (pin "11") (pinfunction "11_11") (pintype "passive"))
      (node (ref "J3") (pin "6") (pinfunction "6_6") (pintype "passive"))
      (node (ref "J3") (pin "9") (pinfunction "9_9") (pintype "passive"))
      (node (ref "J6") (pin "1") (pinfunction "1_1") (pintype "passive"))
      (node (ref "JP1") (pin "2") (pinfunction "2_2") (pintype "passive"))
      (node (ref "Q4") (pin "3") (pinfunction "S_3") (pintype "passive"))
      (node (ref "R17") (pin "2") (pinfunction "2_2") (pintype "passive"))
      (node (ref "R18") (pin "2") (pinfunction "2_2") (pintype "passive"))
      (node (ref "R21") (pin "2") (pinfunction "2_2") (pintype "passive"))
      (node (ref "R24") (pin "2") (pinfunction "2_2") (pintype "passive"))
      (node (ref "R6") (pin "1") (pinfunction "1_1") (pintype "passive"))
      (node (ref "R8") (pin "1") (pinfunction "1_1") (pintype "passive"))
      (node (ref "U1") (pin "1") (pinfunction "VDD_1") (pintype "passive"))
      (node (ref "U2") (pin "8") (pinfunction "Vs+_8") (pintype "power_in"))
      (node (ref "U3") (pin "1") (pinfunction "VREF_1") (pintype "passive"))
      (node (ref "U3") (pin "8") (pinfunction "VDD_8") (pintype "passive"))
      (node (ref "U5") (pin "5") (pinfunction "VOUT_5") (pintype "passive"))
      (node (ref "U6") (pin "3") (pinfunction "VDD_3") (pintype "passive"))
      (node (ref "U7") (pin "4") (pinfunction "VDD/VDDA_4") (pintype "power_in"))
      (node (ref "Y1") (pin "4") (pinfunction "VCC_4") (pintype "power_in"))
    )
    (net (code "2") (name "/BAT-") (class "Default")
      (node (ref "C28") (pin "1") (pinfunction "1_1") (pintype "passive"))
      (node (ref "J5") (pin "2") (pinfunction "2_2") (pintype "passive"))
      (node (ref "Q5") (pin "3") (pinfunction "S_3") (pintype "passive"))
      (node (ref "U9") (pin "3") (pinfunction "VSS_3") (pintype "passive"))
    )
    (net (code "3") (name "/NRST") (class "Default")
      (node (ref "C25") (pin "2") (pinfunction "2_2") (pintype "passive"))
      (node (ref "J6") (pin "10") (pinfunction "10_10") (pintype "passive"))
      (node (ref "Q4") (pin "1") (pinfunction "G_1") (pintype "passive"))
      (node (ref "S3") (pin "2") (pinfunction "2_2") (pintype "passive"))
      (node (ref "U6") (pin "2") (pinfunction "~{RESET}_2") (pintype "passive"))
      (node (ref "U7") (pin "6") (pinfunction "PF2-NRST_6") (pintype "passive"))
    )
    (net (code "4") (name "/SWCLK") (class "Default")
      (node (ref "J6") (pin "4") (pinfunction "4_4") (pintype "passive"))
      (node (ref "R30") (pin "2") (pinfunction "2_2") (pintype "passive"))
      (node (ref "U7") (pin "19") (pinfunction "PA15/PA14-BOOT0_19") (pintype "passive"))
    )
    (net (code "5") (name "/SWDIO") (class "Default")
      (node (ref "J6") (pin "2") (pinfunction "2_2") (pintype "passive"))
      (node (ref "U7") (pin "18") (pinfunction "PA13_18") (pintype "bidirectional"))
    )
    (net (code "6") (name "/SWO") (class "Default")
      (node (ref "J6") (pin "6") (pinfunction "6_6") (pintype "passive+no_connect"))
    )
    (net (code "7") (name "/VD") (class "Default")
      (node (ref "Q5") (pin "2") (pinfunction "D_2") (pintype "passive"))
      (node (ref "Q6") (pin "2") (pinfunction "D_2") (pintype "passive"))
    )
    (net (code "8") (name "/VREF") (class "Default")
      (node (ref "C9") (pin "2") (pinfunction "2_2") (pintype "passive"))
      (node (ref "R10") (pin "1") (pinfunction "1_1") (pintype "passive"))
      (node (ref "R7") (pin "1") (pinfunction "1_1") (pintype "passive"))
      (node (ref "R8") (pin "2") (pinfunction "2_2") (pintype "passive"))
      (node (ref "U4") (pin "1") (pinfunction "K_1") (pintype "passive"))
    )
    (net (code "9") (name "DISP_RST") (class "Default")
      (node (ref "C24") (pin "2") (pinfunction "2_2") (pintype "passive"))
      (node (ref "J3") (pin "14") (pinfunction "14_14") (pintype "passive"))
      (node (ref "R21") (pin "1") (pinfunction "1_1") (pintype "passive"))
      (node (ref "U7") (pin "7") (pinfunction "PA0_7") (pintype "bidirectional"))
    )
    (net (code "10") (name "GAIN_ADJ") (class "Default")
      (node (ref "Q1") (pin "1") (pinfunction "G_1") (pintype "passive"))
      (node (ref "U7") (pin "8") (pinfunction "PA1_8") (pintype "bidirectional"))
    )
    (net (code "11") (name "GAIN_SELECT") (class "Default")
      (node (ref "S1") (pin "2") (pinfunction "2_2") (pintype "passive"))
      (node (ref "U7") (pin "14") (pinfunction "PA7_14") (pintype "bidirectional"))
    )
    (net (code "12") (name "GND") (class "Default")
      (node (ref "C10") (pin "1") (pinfunction "1_1") (pintype "passive"))
      (node (ref "C11") (pin "1") (pinfunction "1_1") (pintype "passive"))
      (node (ref "C12") (pin "1") (pinfunction "1_1") (pintype "passive"))
      (node (ref "C14") (pin "1") (pinfunction "1_1") (pintype "passive"))
      (node (ref "C15") (pin "1") (pinfunction "1_1") (pintype "passive"))
      (node (ref "C17") (pin "1") (pinfunction "1_1") (pintype "passive"))
      (node (ref "C18") (pin "1") (pinfunction "1_1") (pintype "passive"))
      (node (ref "C19") (pin "1") (pinfunction "1_1") (pintype "passive"))
      (node (ref "C2") (pin "1") (pinfunction "1_1") (pintype "passive"))
      (node (ref "C20") (pin "1") (pinfunction "1_1") (pintype "passive"))
      (node (ref "C21") (pin "1") (pinfunction "1_1") (pintype "passive"))
      (node (ref "C22") (pin "1") (pinfunction "1_1") (pintype "passive"))
      (node (ref "C23") (pin "1") (pinfunction "1_1") (pintype "passive"))
      (node (ref "C24") (pin "1") (pinfunction "1_1") (pintype "passive"))
      (node (ref "C25") (pin "1") (pinfunction "1_1") (pintype "passive"))
      (node (ref "C26") (pin "1") (pinfunction "1_1") (pintype "passive"))
      (node (ref "C27") (pin "1") (pinfunction "1_1") (pintype "passive"))
      (node (ref "C29") (pin "1") (pinfunction "1_1") (pintype "passive"))
      (node (ref "C3") (pin "1") (pinfunction "1_1") (pintype "passive"))
      (node (ref "C4") (pin "1") (pinfunction "1_1") (pintype "passive"))
      (node (ref "C5") (pin "1") (pinfunction "1_1") (pintype "passive"))
      (node (ref "C6") (pin "1") (pinfunction "1_1") (pintype "passive"))
      (node (ref "C7") (pin "1") (pinfunction "1_1") (pintype "passive"))
      (node (ref "C8") (pin "1") (pinfunction "1_1") (pintype "passive"))
      (node (ref "C9") (pin "1") (pinfunction "1_1") (pintype "passive"))
      (node (ref "D6") (pin "2") (pinfunction "K_2") (pintype "passive"))
      (node (ref "J1") (pin "1") (pinfunction "S_1") (pintype "power_in"))
      (node (ref "J2") (pin "1") (pinfunction "SHLD_1") (pintype "passive"))
      (node (ref "J2") (pin "2") (pinfunction "SHLD_2") (pintype "passive"))
      (node (ref "J2") (pin "3") (pinfunction "SHLD_3") (pintype "passive"))
      (node (ref "J2") (pin "4") (pinfunction "SHLD_4") (pintype "passive"))
      (node (ref "J2") (pin "A1_B12") (pinfunction "GND_A1_B12") (pintype "passive"))
      (node (ref "J2") (pin "B1_A12") (pinfunction "GND_B1_A12") (pintype "passive"))
      (node (ref "J3") (pin "1") (pinfunction "1_1") (pintype "passive"))
      (node (ref "J3") (pin "10") (pinfunction "10_10") (pintype "passive"))
      (node (ref "J3") (pin "12") (pinfunction "12_12") (pintype "passive"))
      (node (ref "J3") (pin "13") (pinfunction "13_13") (pintype "passive"))
      (node (ref "J3") (pin "15") (pinfunction "15_15") (pintype "passive"))
      (node (ref "J3") (pin "29") (pinfunction "29_29") (pintype "passive"))
      (node (ref "J3") (pin "30") (pinfunction "30_30") (pintype "passive"))
      (node (ref "J3") (pin "8") (pinfunction "8_8") (pintype "passive"))
      (node (ref "J4") (pin "6") (pinfunction "6_6") (pintype "passive"))
      (node (ref "J6") (pin "3") (pinfunction "3_3") (pintype "passive"))
      (node (ref "Q1") (pin "3") (pinfunction "S_3") (pintype "passive"))
      (node (ref "Q6") (pin "3") (pinfunction "S_3") (pintype "passive"))
      (node (ref "R12") (pin "2") (pinfunction "2_2") (pintype "passive"))
      (node (ref "R13") (pin "1") (pinfunction "1_1") (pintype "passive"))
      (node (ref "R14") (pin "1") (pinfunction "1_1") (pintype "passive"))
      (node (ref "R16") (pin "1") (pinfunction "1_1") (pintype "passive"))
      (node (ref "R19") (pin "2") (pinfunction "2_2") (pintype "passive"))
      (node (ref "R2") (pin "1") (pinfunction "1_1") (pintype "passive"))
      (node (ref "R20") (pin "2") (pinfunction "2_2") (pintype "passive"))
      (node (ref "R26") (pin "1") (pinfunction "1_1") (pintype "passive"))
      (node (ref "R27") (pin "2") (pinfunction "2_2") (pintype "passive"))
      (node (ref "R29") (pin "1") (pinfunction "1_1") (pintype "passive"))
      (node (ref "R30") (pin "1") (pinfunction "1_1") (pintype "passive"))
      (node (ref "R32") (pin "2") (pinfunction "2_2") (pintype "passive"))
      (node (ref "S1") (pin "1") (pinfunction "1_1") (pintype "passive"))
      (node (ref "S3") (pin "1") (pinfunction "1_1") (pintype "passive"))
      (node (ref "U1") (pin "2") (pinfunction "VSS_2") (pintype "power_in"))
      (node (ref "U2") (pin "4") (pinfunction "Vs-_4") (pintype "power_in"))
      (node (ref "U3") (pin "3") (pinfunction "IN-_3") (pintype "passive"))
      (node (ref "U3") (pin "4") (pinfunction "VSS_4") (pintype "power_in"))
      (node (ref "U4") (pin "3") (pinfunction "A_3") (pintype "passive"))
      (node (ref "U5") (pin "2") (pinfunction "GND_2") (pintype "passive"))
      (node (ref "U5") (pin "4") (pinfunction "GND_4") (pintype "passive"))
      (node (ref "U6") (pin "1") (pinfunction "GND_1") (pintype "passive"))
      (node (ref "U7") (pin "5") (pinfunction "VSS/VSSA_5") (pintype "power_in"))
      (node (ref "U8") (pin "5") (pinfunction "VSS_5") (pintype "power_in"))
      (node (ref "Y1") (pin "2") (pinfunction "GND_2") (pintype "passive"))
    )
    (net (code "13") (name "MCU_SCL") (class "Default")
      (node (ref "J3") (pin "18") (pinfunction "18_18") (pintype "passive"))
      (node (ref "R18") (pin "1") (pinfunction "1_1") (pintype "passive"))
      (node (ref "U7") (pin "20") (pinfunction "PB3/PB4/PB5/PB6_20") (pintype "bidirectional"))
    )
    (net (code "14") (name "MCU_SDA") (class "Default")
      (node (ref "J3") (pin "19") (pinfunction "19_19") (pintype "passive"))
      (node (ref "J3") (pin "20") (pinfunction "20_20") (pintype "passive"))
      (node (ref "R17") (pin "1") (pinfunction "1_1") (pintype "passive"))
      (node (ref "U7") (pin "1") (pinfunction "PB7/PB8_1") (pintype "bidirectional"))
    )
    (net (code "15") (name "MCU_SPI_NSS") (class "Default")
      (node (ref "J4") (pin "1") (pinfunction "1_1") (pintype "passive"))
      (node (ref "U3") (pin "5") (pinfunction "~{CS}_5") (pintype "passive"))
      (node (ref "U7") (pin "11") (pinfunction "PA4_11") (pintype "bidirectional"))
    )
    (net (code "16") (name "MCU_SPI_SCK") (class "Default")
      (node (ref "J4") (pin "3") (pinfunction "3_3") (pintype "passive"))
      (node (ref "U3") (pin "7") (pinfunction "CLK_7") (pintype "passive"))
      (node (ref "U7") (pin "12") (pinfunction "PA5_12") (pintype "bidirectional"))
    )
    (net (code "17") (name "MCU_SPI_SDI") (class "Default")
      (node (ref "J4") (pin "2") (pinfunction "2_2") (pintype "passive"))
      (node (ref "U3") (pin "6") (pinfunction "DOUT_6") (pintype "passive"))
      (node (ref "U7") (pin "13") (pinfunction "PA6_13") (pintype "bidirectional"))
    )
    (net (code "18") (name "MSG_CLK") (class "Default")
      (node (ref "J4") (pin "5") (pinfunction "5_5") (pintype "passive"))
      (node (ref "U1") (pin "4") (pinfunction "STROBE_4") (pintype "passive"))
      (node (ref "U7") (pin "10") (pinfunction "PA3_10") (pintype "bidirectional"))
    )
    (net (code "19") (name "MSG_OUT") (class "Default")
      (node (ref "R9") (pin "1") (pinfunction "1_1") (pintype "passive"))
      (node (ref "U1") (pin "3") (pinfunction "OUT_3") (pintype "passive"))
    )
    (net (code "20") (name "MSG_RST") (class "Default")
      (node (ref "J4") (pin "4") (pinfunction "4_4") (pintype "passive"))
      (node (ref "U1") (pin "7") (pinfunction "~{RESET}_7") (pintype "passive"))
      (node (ref "U7") (pin "9") (pinfunction "PA2_9") (pintype "bidirectional"))
    )
    (net (code "21") (name "Net-(C3-Pad2)") (class "Default")
      (node (ref "C3") (pin "2") (pinfunction "2_2") (pintype "passive"))
      (node (ref "R4") (pin "2") (pinfunction "2_2") (pintype "passive"))
      (node (ref "R5") (pin "1") (pinfunction "1_1") (pintype "passive"))
    )
    (net (code "22") (name "Net-(C13-Pad1)") (class "Default")
      (node (ref "C13") (pin "1") (pinfunction "1_1") (pintype "passive"))
      (node (ref "J3") (pin "2") (pinfunction "2_2") (pintype "passive"))
    )
    (net (code "23") (name "Net-(C13-Pad2)") (class "Default")
      (node (ref "C13") (pin "2") (pinfunction "2_2") (pintype "passive"))
      (node (ref "J3") (pin "3") (pinfunction "3_3") (pintype "passive"))
    )
    (net (code "24") (name "Net-(C16-Pad1)") (class "Default")
      (node (ref "C16") (pin "1") (pinfunction "1_1") (pintype "passive"))
      (node (ref "J3") (pin "4") (pinfunction "4_4") (pintype "passive"))
    )
    (net (code "25") (name "Net-(C16-Pad2)") (class "Default")
      (node (ref "C16") (pin "2") (pinfunction "2_2") (pintype "passive"))
      (node (ref "J3") (pin "5") (pinfunction "5_5") (pintype "passive"))
    )
    (net (code "26") (name "Net-(C26-Pad2)") (class "Default")
      (node (ref "C26") (pin "2") (pinfunction "2_2") (pintype "passive"))
      (node (ref "J3") (pin "27") (pinfunction "27_27") (pintype "passive"))
    )
    (net (code "27") (name "Net-(C27-Pad2)") (class "Default")
      (node (ref "C27") (pin "2") (pinfunction "2_2") (pintype "passive"))
      (node (ref "J3") (pin "28") (pinfunction "28_28") (pintype "passive"))
    )
    (net (code "28") (name "Net-(D1-K)") (class "Default")
      (node (ref "C15") (pin "2") (pinfunction "2_2") (pintype "passive"))
      (node (ref "D1") (pin "2") (pinfunction "K_2") (pintype "passive"))
      (node (ref "Q2") (pin "3") (pinfunction "S_3") (pintype "passive"))
      (node (ref "Q3") (pin "3") (pinfunction "S_3") (pintype "passive"))
      (node (ref "R15") (pin "2") (pinfunction "2_2") (pintype "passive"))
    )
    (net (code "29") (name "Net-(D2-A)") (class "Default")
      (node (ref "D2") (pin "1") (pinfunction "A_1") (pintype "passive"))
      (node (ref "R22") (pin "2") (pinfunction "2_2") (pintype "passive"))
    )
    (net (code "30") (name "Net-(D2-K)") (class "Default")
      (node (ref "D2") (pin "2") (pinfunction "K_2") (pintype "passive"))
      (node (ref "U8") (pin "3") (pinfunction "STAT1_3") (pintype "input"))
    )
    (net (code "31") (name "Net-(D3-A)") (class "Default")
      (node (ref "D3") (pin "1") (pinfunction "A_1") (pintype "passive"))
      (node (ref "R23") (pin "2") (pinfunction "2_2") (pintype "passive"))
    )
    (net (code "32") (name "Net-(D3-K)") (class "Default")
      (node (ref "D3") (pin "2") (pinfunction "K_2") (pintype "passive"))
      (node (ref "U8") (pin "4") (pinfunction "STAT2_4") (pintype "input"))
    )
    (net (code "33") (name "Net-(D4-A)") (class "Default")
      (node (ref "D4") (pin "1") (pinfunction "A_1") (pintype "passive"))
      (node (ref "R25") (pin "2") (pinfunction "2_2") (pintype "passive"))
    )
    (net (code "34") (name "Net-(D4-K)") (class "Default")
      (node (ref "D4") (pin "2") (pinfunction "K_2") (pintype "passive"))
      (node (ref "U8") (pin "7") (pinfunction "~{PG}_7") (pintype "input"))
    )
    (net (code "35") (name "Net-(D5-A)") (class "Default")
      (node (ref "D5") (pin "1") (pinfunction "A_1") (pintype "passive"))
      (node (ref "R24") (pin "1") (pinfunction "1_1") (pintype "passive"))
    )
    (net (code "36") (name "Net-(D5-K)") (class "Default")
      (node (ref "D5") (pin "2") (pinfunction "K_2") (pintype "passive"))
      (node (ref "U7") (pin "3") (pinfunction "PC15-OSC32_OUT_3") (pintype "bidirectional"))
    )
    (net (code "37") (name "Net-(D6-A)") (class "Default")
      (node (ref "D6") (pin "1") (pinfunction "A_1") (pintype "passive"))
      (node (ref "R31") (pin "1") (pinfunction "1_1") (pintype "passive"))
    )
    (net (code "38") (name "Net-(J1-T)") (class "Default")
      (node (ref "J1") (pin "3") (pinfunction "T_3") (pintype "passive"))
      (node (ref "R4") (pin "1") (pinfunction "1_1") (pintype "passive"))
    )
    (net (code "39") (name "Net-(J2-CC1)") (class "Default")
      (node (ref "J2") (pin "A5") (pinfunction "CC1_A5") (pintype "passive"))
      (node (ref "R14") (pin "2") (pinfunction "2_2") (pintype "passive"))
    )
    (net (code "40") (name "Net-(J2-CC2)") (class "Default")
      (node (ref "J2") (pin "B5") (pinfunction "CC2_B5") (pintype "passive"))
      (node (ref "R13") (pin "2") (pinfunction "2_2") (pintype "passive"))
    )
    (net (code "41") (name "Net-(J3-Pad26)") (class "Default")
      (node (ref "J3") (pin "26") (pinfunction "26_26") (pintype "passive"))
      (node (ref "R29") (pin "2") (pinfunction "2_2") (pintype "passive"))
    )
    (net (code "42") (name "Net-(J6-Pad5)") (class "Default")
      (node (ref "J6") (pin "5") (pinfunction "5_5") (pintype "passive"))
      (node (ref "JP1") (pin "1") (pinfunction "1_1") (pintype "passive"))
    )
    (net (code "43") (name "Net-(Q1-D)") (class "Default")
      (node (ref "Q1") (pin "2") (pinfunction "D_2") (pintype "passive"))
      (node (ref "R1") (pin "1") (pinfunction "1_1") (pintype "passive"))
    )
    (net (code "44") (name "Net-(Q3-D)") (class "Default")
      (node (ref "C17") (pin "2") (pinfunction "2_2") (pintype "passive"))
      (node (ref "Q3") (pin "2") (pinfunction "D_2") (pintype "passive"))
      (node (ref "U5") (pin "1") (pinfunction "VIN_1") (pintype "passive"))
      (node (ref "U5") (pin "3") (pinfunction "EN_3") (pintype "passive"))
    )
    (net (code "45") (name "Net-(Q3-G)") (class "Default")
      (node (ref "Q3") (pin "1") (pinfunction "G_1") (pintype "passive"))
      (node (ref "R15") (pin "1") (pinfunction "1_1") (pintype "passive"))
      (node (ref "S2") (pin "2") (pinfunction "COM_2") (pintype "passive"))
    )
    (net (code "46") (name "Net-(Q4-D)") (class "Default")
      (node (ref "Q4") (pin "2") (pinfunction "D_2") (pintype "passive"))
      (node (ref "R31") (pin "2") (pinfunction "2_2") (pintype "passive"))
    )
    (net (code "47") (name "Net-(Q5-G)") (class "Default")
      (node (ref "Q5") (pin "1") (pinfunction "G_1") (pintype "passive"))
      (node (ref "U9") (pin "4") (pinfunction "DO_4") (pintype "passive"))
    )
    (net (code "48") (name "Net-(Q6-G)") (class "Default")
      (node (ref "Q6") (pin "1") (pinfunction "G_1") (pintype "passive"))
      (node (ref "U9") (pin "5") (pinfunction "CO_5") (pintype "passive"))
    )
    (net (code "49") (name "Net-(S2-A)") (class "Default")
      (node (ref "R19") (pin "1") (pinfunction "1_1") (pintype "passive"))
      (node (ref "S2") (pin "1") (pinfunction "A_1") (pintype "passive"))
    )
    (net (code "50") (name "Net-(S2-B)") (class "Default")
      (node (ref "R20") (pin "1") (pinfunction "1_1") (pintype "passive"))
      (node (ref "S2") (pin "3") (pinfunction "B_3") (pintype "passive"))
    )
    (net (code "51") (name "Net-(U1-AUDIO_IN)") (class "Default")
      (node (ref "C1") (pin "1") (pinfunction "1_1") (pintype "passive"))
      (node (ref "U1") (pin "5") (pinfunction "AUDIO_IN_5") (pintype "passive"))
    )
    (net (code "52") (name "Net-(U1-CKIN)") (class "Default")
      (node (ref "C7") (pin "2") (pinfunction "2_2") (pintype "passive"))
      (node (ref "R6") (pin "2") (pinfunction "2_2") (pintype "passive"))
      (node (ref "U1") (pin "8") (pinfunction "CKIN_8") (pintype "passive"))
    )
    (net (code "53") (name "Net-(U1-GNDREF)") (class "Default")
      (node (ref "C6") (pin "2") (pinfunction "2_2") (pintype "passive"))
      (node (ref "U1") (pin "6") (pinfunction "GNDREF_6") (pintype "power_in"))
    )
    (net (code "54") (name "Net-(U2A-+)") (class "Default")
      (node (ref "C10") (pin "2") (pinfunction "2_2") (pintype "passive"))
      (node (ref "R9") (pin "2") (pinfunction "2_2") (pintype "passive"))
      (node (ref "U2") (pin "3") (pinfunction "+_3") (pintype "passive"))
    )
    (net (code "55") (name "Net-(U2A--)") (class "Default")
      (node (ref "U2") (pin "1") (pinfunction "OUT_1") (pintype "passive"))
      (node (ref "U2") (pin "2") (pinfunction "-_2") (pintype "passive"))
      (node (ref "U3") (pin "2") (pinfunction "IN+_2") (pintype "passive"))
    )
    (net (code "56") (name "Net-(U2B-+)") (class "Default")
      (node (ref "R5") (pin "2") (pinfunction "2_2") (pintype "passive"))
      (node (ref "R7") (pin "2") (pinfunction "2_2") (pintype "passive"))
      (node (ref "U2") (pin "5") (pinfunction "+_5") (pintype "passive"))
    )
    (net (code "57") (name "Net-(U2B--)") (class "Default")
      (node (ref "R1") (pin "2") (pinfunction "2_2") (pintype "passive"))
      (node (ref "R2") (pin "2") (pinfunction "2_2") (pintype "passive"))
      (node (ref "R3") (pin "1") (pinfunction "1_1") (pintype "passive"))
      (node (ref "U2") (pin "6") (pinfunction "-_6") (pintype "passive"))
    )
    (net (code "58") (name "Net-(U2B-OUT)") (class "Default")
      (node (ref "C1") (pin "2") (pinfunction "2_2") (pintype "passive"))
      (node (ref "R3") (pin "2") (pinfunction "2_2") (pintype "passive"))
      (node (ref "U2") (pin "7") (pinfunction "OUT_7") (pintype "passive"))
    )
    (net (code "59") (name "Net-(U4-REF)") (class "Default")
      (node (ref "R10") (pin "2") (pinfunction "2_2") (pintype "passive"))
      (node (ref "R12") (pin "1") (pinfunction "1_1") (pintype "passive"))
      (node (ref "U4") (pin "2") (pinfunction "REF_2") (pintype "passive"))
    )
    (net (code "60") (name "Net-(U7-PB9{slash}PC14-OSC32_IN)") (class "Default")
      (node (ref "U7") (pin "2") (pinfunction "PB9/PC14-OSC32_IN_2") (pintype "bidirectional"))
      (node (ref "Y1") (pin "3") (pinfunction "OUT_3") (pintype "passive"))
    )
    (net (code "61") (name "Net-(U8-PROG)") (class "Default")
      (node (ref "R27") (pin "1") (pinfunction "1_1") (pintype "passive"))
      (node (ref "U8") (pin "6") (pinfunction "PROG_6") (pintype "output"))
    )
    (net (code "62") (name "Net-(U8-THERM)") (class "Default")
      (node (ref "R26") (pin "2") (pinfunction "2_2") (pintype "passive"))
      (node (ref "U8") (pin "8") (pinfunction "THERM_8") (pintype "input"))
    )
    (net (code "63") (name "Net-(U9-VDD)") (class "Default")
      (node (ref "C28") (pin "2") (pinfunction "2_2") (pintype "passive"))
      (node (ref "R28") (pin "2") (pinfunction "2_2") (pintype "passive"))
      (node (ref "U9") (pin "2") (pinfunction "VDD_2") (pintype "passive"))
    )
    (net (code "64") (name "Net-(U9-VM)") (class "Default")
      (node (ref "R32") (pin "1") (pinfunction "1_1") (pintype "passive"))
      (node (ref "U9") (pin "1") (pinfunction "VM_1") (pintype "passive"))
    )
    (net (code "65") (name "USB_N") (class "Default")
      (node (ref "J2") (pin "A7") (pinfunction "D-_A7") (pintype "passive"))
      (node (ref "J2") (pin "B7") (pinfunction "D-_B7") (pintype "passive"))
      (node (ref "R11") (pin "1") (pinfunction "1_1") (pintype "passive"))
    )
    (net (code "66") (name "USB_P") (class "Default")
      (node (ref "J2") (pin "A6") (pinfunction "D+_A6") (pintype "passive"))
      (node (ref "J2") (pin "B6") (pinfunction "D+_B6") (pintype "passive"))
      (node (ref "R11") (pin "2") (pinfunction "2_2") (pintype "passive"))
    )
    (net (code "67") (name "VBAT") (class "Default")
      (node (ref "C23") (pin "2") (pinfunction "2_2") (pintype "passive"))
      (node (ref "J5") (pin "1") (pinfunction "1_1") (pintype "passive"))
      (node (ref "Q2") (pin "2") (pinfunction "D_2") (pintype "passive"))
      (node (ref "R28") (pin "1") (pinfunction "1_1") (pintype "passive"))
      (node (ref "U8") (pin "10") (pinfunction "VBAT_10") (pintype "power_in"))
      (node (ref "U8") (pin "9") (pinfunction "VBAT_9") (pintype "power_in"))
    )
    (net (code "68") (name "VBUS") (class "Default")
      (node (ref "C22") (pin "2") (pinfunction "2_2") (pintype "passive"))
      (node (ref "C8") (pin "2") (pinfunction "2_2") (pintype "passive"))
      (node (ref "D1") (pin "1") (pinfunction "A_1") (pintype "passive"))
      (node (ref "J2") (pin "A4_B9") (pinfunction "VBUS_A4_B9") (pintype "passive"))
      (node (ref "J2") (pin "B4_A9") (pinfunction "VBUS_B4_A9") (pintype "passive"))
      (node (ref "Q2") (pin "1") (pinfunction "G_1") (pintype "passive"))
      (node (ref "R16") (pin "2") (pinfunction "2_2") (pintype "passive"))
      (node (ref "R22") (pin "1") (pinfunction "1_1") (pintype "passive"))
      (node (ref "R23") (pin "1") (pinfunction "1_1") (pintype "passive"))
      (node (ref "R25") (pin "1") (pinfunction "1_1") (pintype "passive"))
      (node (ref "U8") (pin "1") (pinfunction "VDD_1") (pintype "power_in"))
      (node (ref "U8") (pin "2") (pinfunction "VDD_2") (pintype "power_in"))
    )
    (net (code "69") (name "unconnected-(J1-R-Pad2)") (class "Default")
      (node (ref "J1") (pin "2") (pinfunction "R_2") (pintype "passive+no_connect"))
    )
    (net (code "70") (name "unconnected-(J3-Pad7)") (class "Default")
      (node (ref "J3") (pin "7") (pinfunction "7_7") (pintype "passive+no_connect"))
    )
    (net (code "71") (name "unconnected-(J3-Pad16)") (class "Default")
      (node (ref "J3") (pin "16") (pinfunction "16_16") (pintype "passive+no_connect"))
    )
    (net (code "72") (name "unconnected-(J3-Pad17)") (class "Default")
      (node (ref "J3") (pin "17") (pinfunction "17_17") (pintype "passive+no_connect"))
    )
    (net (code "73") (name "unconnected-(J3-Pad21)") (class "Default")
      (node (ref "J3") (pin "21") (pinfunction "21_21") (pintype "passive+no_connect"))
    )
    (net (code "74") (name "unconnected-(J3-Pad22)") (class "Default")
      (node (ref "J3") (pin "22") (pinfunction "22_22") (pintype "passive+no_connect"))
    )
    (net (code "75") (name "unconnected-(J3-Pad23)") (class "Default")
      (node (ref "J3") (pin "23") (pinfunction "23_23") (pintype "passive+no_connect"))
    )
    (net (code "76") (name "unconnected-(J3-Pad24)") (class "Default")
      (node (ref "J3") (pin "24") (pinfunction "24_24") (pintype "passive+no_connect"))
    )
    (net (code "77") (name "unconnected-(J3-Pad25)") (class "Default")
      (node (ref "J3") (pin "25") (pinfunction "25_25") (pintype "passive+no_connect"))
    )
    (net (code "78") (name "unconnected-(J3-PadS1)") (class "Default")
      (node (ref "J3") (pin "S1") (pinfunction "S1_S1") (pintype "passive+no_connect"))
    )
    (net (code "79") (name "unconnected-(J3-PadS2)") (class "Default")
      (node (ref "J3") (pin "S2") (pinfunction "S2_S2") (pintype "passive+no_connect"))
    )
    (net (code "80") (name "unconnected-(J5-PadS1)") (class "Default")
      (node (ref "J5") (pin "S1") (pinfunction "S1_S1") (pintype "passive+no_connect"))
    )
    (net (code "81") (name "unconnected-(J5-PadS2)") (class "Default")
      (node (ref "J5") (pin "S2") (pinfunction "S2_S2") (pintype "passive+no_connect"))
    )
    (net (code "82") (name "unconnected-(J6-Pad7)") (class "Default")
      (node (ref "J6") (pin "7") (pinfunction "7_7") (pintype "passive+no_connect"))
    )
    (net (code "83") (name "unconnected-(J6-Pad8)") (class "Default")
      (node (ref "J6") (pin "8") (pinfunction "8_8") (pintype "passive+no_connect"))
    )
    (net (code "84") (name "unconnected-(J6-Pad9)") (class "Default")
      (node (ref "J6") (pin "9") (pinfunction "9_9") (pintype "passive+no_connect"))
    )
    (net (code "85") (name "unconnected-(S2-S1-Pad4)") (class "Default")
      (node (ref "S2") (pin "4") (pinfunction "S1_4") (pintype "passive+no_connect"))
    )
    (net (code "86") (name "unconnected-(S2-S2-Pad5)") (class "Default")
      (node (ref "S2") (pin "5") (pinfunction "S2_5") (pintype "passive+no_connect"))
    )
    (net (code "87") (name "unconnected-(U7-PA11{slash}PA9-Pad16)") (class "Default")
      (node (ref "U7") (pin "16") (pinfunction "PA11/PA9_16") (pintype "bidirectional+no_connect"))
    )
    (net (code "88") (name "unconnected-(U7-PA12{slash}PA10-Pad17)") (class "Default")
      (node (ref "U7") (pin "17") (pinfunction "PA12/PA10_17") (pintype "bidirectional+no_connect"))
    )
    (net (code "89") (name "unconnected-(U7-PB0{slash}PB1{slash}PB2{slash}PA8-Pad15)") (class "Default")
      (node (ref "U7") (pin "15") (pinfunction "PB0/PB1/PB2/PA8_15") (pintype "bidirectional+no_connect"))
    )
    (net (code "90") (name "unconnected-(Y1-E{slash}D-Pad1)") (class "Default")
      (node (ref "Y1") (pin "1") (pinfunction "E/D_1") (pintype "passive+no_connect"))
    )
  )
)
